# Power.net
KiCad netlist of a schematic drawn in Altium Designer
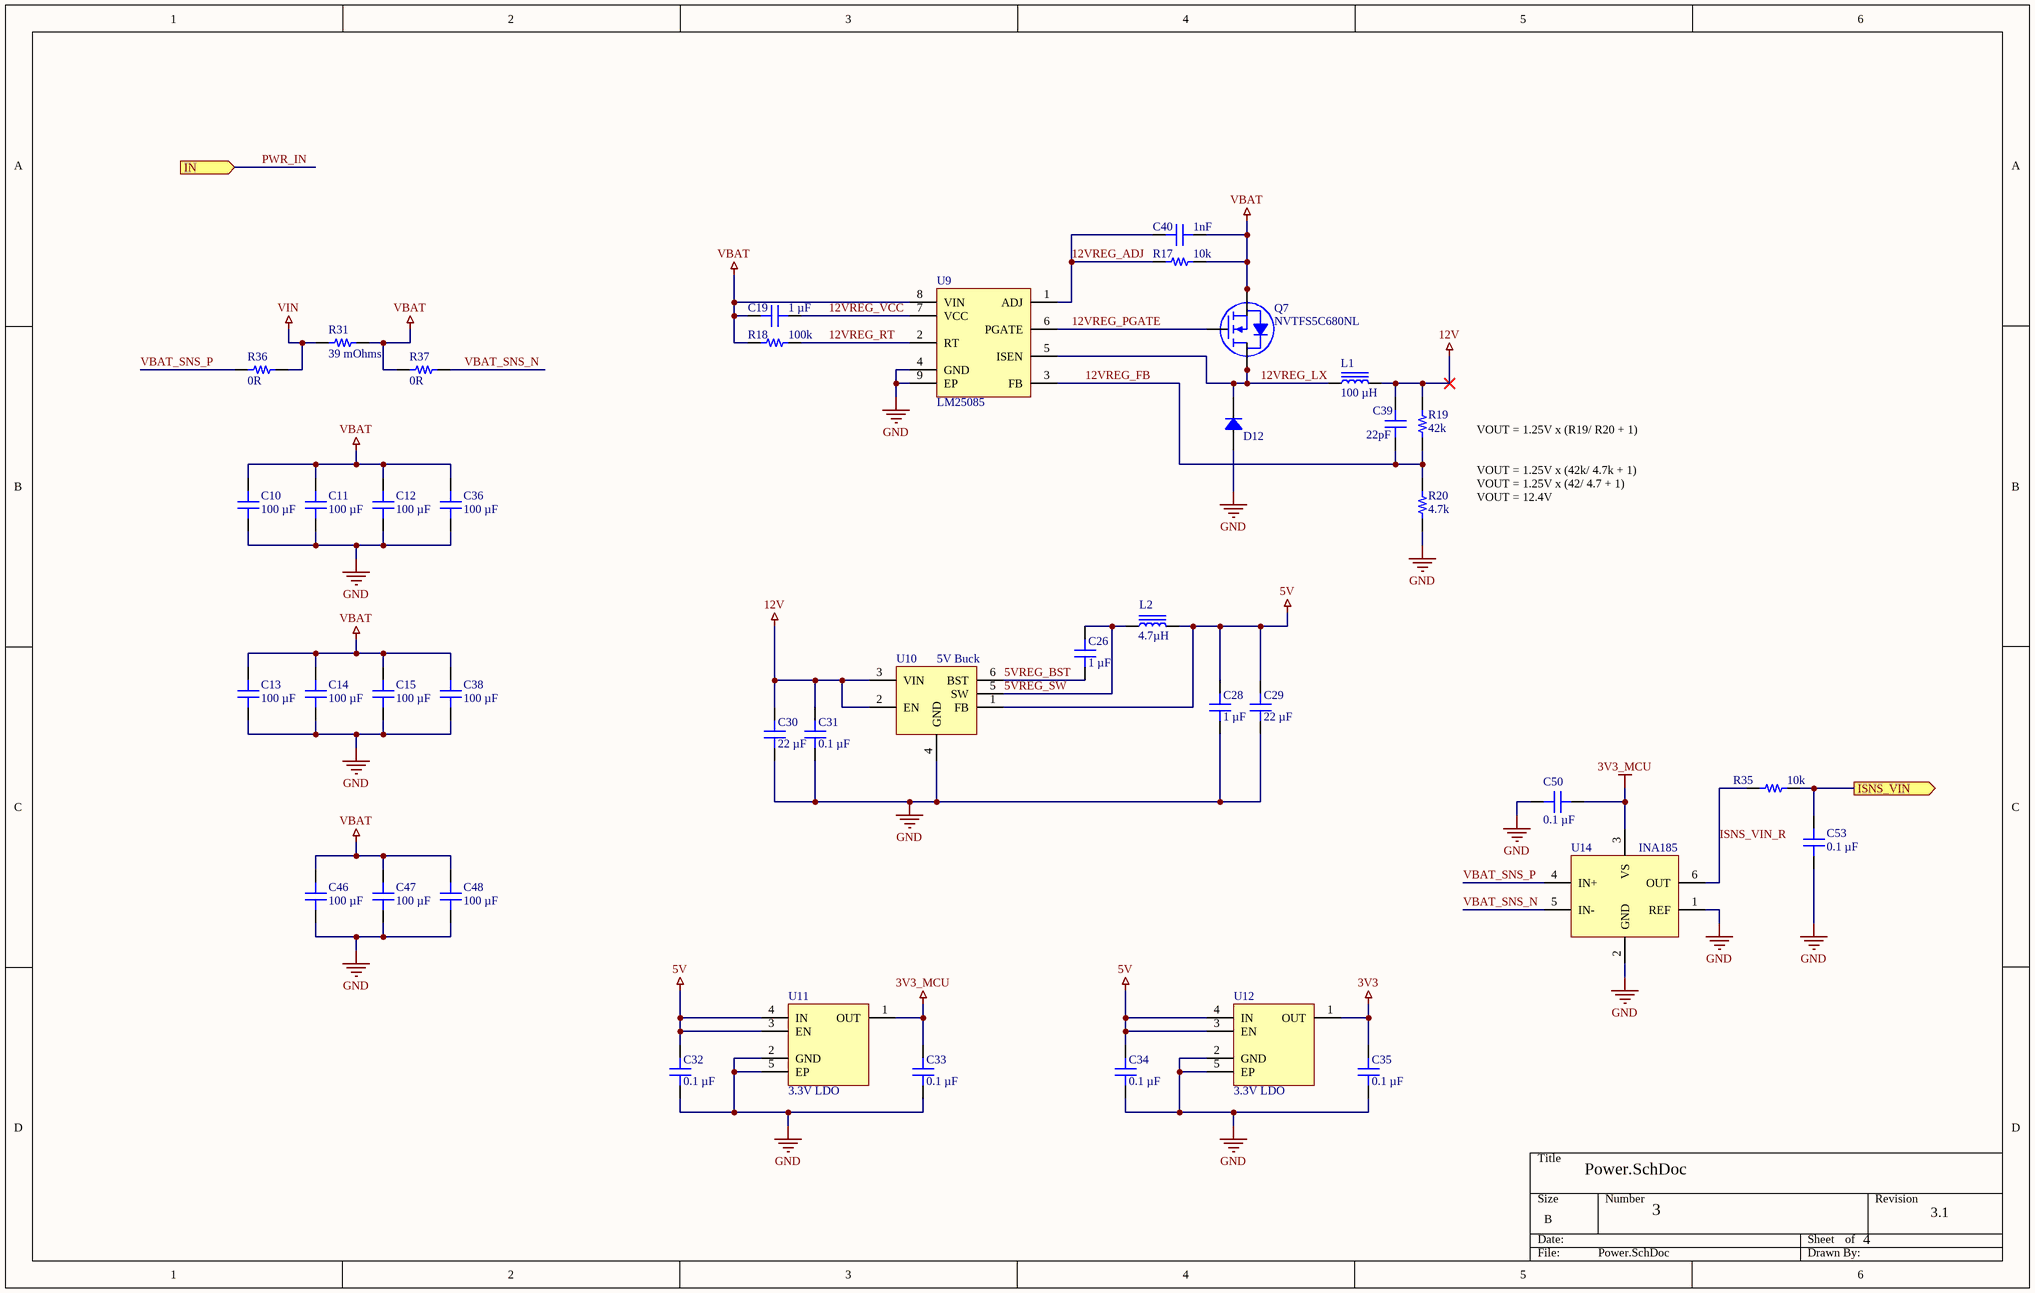
[diagram p0: Power.SchDoc]

(export (version "E")
  (design (tool "Eeschema 10.0.6"))
  (components
    (comp (ref "C10")
      (value "100 µF")
      (footprint "CAP 1210_3225 - 1MM")
      (description "CAP CER 100UF 16V X5R 1210")
      (fields (field (name "PART NUMBER") "MSASE32MAB5107MPNA01") (field (name "MANUFACTURER") "Taiyo Yuden"))
      (libsource (lib "Celestial Altium Library - altium_library") (part "Capacitor"))
    )
    (comp (ref "C11")
      (value "100 µF")
      (footprint "CAP 1210_3225 - 1MM")
      (description "CAP CER 100UF 16V X5R 1210")
      (fields (field (name "PART NUMBER") "MSASE32MAB5107MPNA01") (field (name "MANUFACTURER") "Taiyo Yuden"))
      (libsource (lib "Celestial Altium Library - altium_library") (part "Capacitor"))
    )
    (comp (ref "C12")
      (value "100 µF")
      (footprint "CAP 1210_3225 - 1MM")
      (description "CAP CER 100UF 16V X5R 1210")
      (fields (field (name "PART NUMBER") "MSASE32MAB5107MPNA01") (field (name "MANUFACTURER") "Taiyo Yuden"))
      (libsource (lib "Celestial Altium Library - altium_library") (part "Capacitor"))
    )
    (comp (ref "C13")
      (value "100 µF")
      (footprint "CAP 1210_3225 - 1MM")
      (description "CAP CER 100UF 16V X5R 1210")
      (fields (field (name "PART NUMBER") "MSASE32MAB5107MPNA01") (field (name "MANUFACTURER") "Taiyo Yuden"))
      (libsource (lib "Celestial Altium Library - altium_library") (part "Capacitor"))
    )
    (comp (ref "C14")
      (value "100 µF")
      (footprint "CAP 1210_3225 - 1MM")
      (description "CAP CER 100UF 16V X5R 1210")
      (fields (field (name "PART NUMBER") "MSASE32MAB5107MPNA01") (field (name "MANUFACTURER") "Taiyo Yuden"))
      (libsource (lib "Celestial Altium Library - altium_library") (part "Capacitor"))
    )
    (comp (ref "C15")
      (value "100 µF")
      (footprint "CAP 1210_3225 - 1MM")
      (description "CAP CER 100UF 16V X5R 1210")
      (fields (field (name "PART NUMBER") "MSASE32MAB5107MPNA01") (field (name "MANUFACTURER") "Taiyo Yuden"))
      (libsource (lib "Celestial Altium Library - altium_library") (part "Capacitor"))
    )
    (comp (ref "C19")
      (value "1 µF")
      (footprint "CAP 0402_1005")
      (description "CAP CER 0.1UF 16V X7R 0402")
      (fields (field (name "PART NUMBER") "C0402C104K4RACAUTO") (field (name "MANUFACTURER") "KEMET"))
      (libsource (lib "Celestial Altium Library - altium_library") (part "Capacitor"))
    )
    (comp (ref "C26")
      (value "1 µF")
      (footprint "CAP 0402_1005")
      (description "CAP CER 0.1UF 16V X7R 0402")
      (fields (field (name "PART NUMBER") "C0402C104K4RACAUTO") (field (name "MANUFACTURER") "KEMET"))
      (libsource (lib "Celestial Altium Library - altium_library") (part "Capacitor"))
    )
    (comp (ref "C28")
      (value "1 µF")
      (footprint "CAP 0402_1005")
      (description "CAP CER 0.1UF 16V X7R 0402")
      (fields (field (name "PART NUMBER") "C0402C104K4RACAUTO") (field (name "MANUFACTURER") "KEMET"))
      (libsource (lib "Celestial Altium Library - altium_library") (part "Capacitor"))
    )
    (comp (ref "C29")
      (value "22 µF")
      (footprint "CAP 0402_1005")
      (description "CAP CER 0.1UF 16V X7R 0402")
      (fields (field (name "PART NUMBER") "C0402C104K4RACAUTO") (field (name "MANUFACTURER") "KEMET"))
      (libsource (lib "Celestial Altium Library - altium_library") (part "Capacitor"))
    )
    (comp (ref "C30")
      (value "22 µF")
      (footprint "CAP 0603_1608")
      (description "CAP CER 47UF 6.3V X5R 0603")
      (fields
        (field (name "PART NUMBER") "C0603B476M007T")
        (field (name "MANUFACTURER") "Holy Stone Enterprise Co., Ltd.")
      )
      (libsource (lib "Celestial Altium Library - altium_library") (part "Capacitor"))
    )
    (comp (ref "C31")
      (value "0.1 µF")
      (footprint "CAP 0402_1005")
      (description "CAP CER 0.1UF 16V X7R 0402")
      (fields (field (name "PART NUMBER") "C0402C104K4RACAUTO") (field (name "MANUFACTURER") "KEMET"))
      (libsource (lib "Celestial Altium Library - altium_library") (part "Capacitor"))
    )
    (comp (ref "C32")
      (value "0.1 µF")
      (footprint "CAP 0402_1005")
      (description "CAP CER 0.1UF 16V X7R 0402")
      (fields (field (name "PART NUMBER") "C0402C104K4RACAUTO") (field (name "MANUFACTURER") "KEMET"))
      (libsource (lib "Celestial Altium Library - altium_library") (part "Capacitor"))
    )
    (comp (ref "C33")
      (value "0.1 µF")
      (footprint "CAP 0402_1005")
      (description "CAP CER 0.1UF 16V X7R 0402")
      (fields (field (name "PART NUMBER") "C0402C104K4RACAUTO") (field (name "MANUFACTURER") "KEMET"))
      (libsource (lib "Celestial Altium Library - altium_library") (part "Capacitor"))
    )
    (comp (ref "C34")
      (value "0.1 µF")
      (footprint "CAP 0402_1005")
      (description "CAP CER 0.1UF 16V X7R 0402")
      (fields (field (name "PART NUMBER") "C0402C104K4RACAUTO") (field (name "MANUFACTURER") "KEMET"))
      (libsource (lib "Celestial Altium Library - altium_library") (part "Capacitor"))
    )
    (comp (ref "C35")
      (value "0.1 µF")
      (footprint "CAP 0402_1005")
      (description "CAP CER 0.1UF 16V X7R 0402")
      (fields (field (name "PART NUMBER") "C0402C104K4RACAUTO") (field (name "MANUFACTURER") "KEMET"))
      (libsource (lib "Celestial Altium Library - altium_library") (part "Capacitor"))
    )
    (comp (ref "C36")
      (value "100 µF")
      (footprint "CAP 1210_3225 - 1MM")
      (description "CAP CER 100UF 16V X5R 1210")
      (fields (field (name "PART NUMBER") "MSASE32MAB5107MPNA01") (field (name "MANUFACTURER") "Taiyo Yuden"))
      (libsource (lib "Celestial Altium Library - altium_library") (part "Capacitor"))
    )
    (comp (ref "C38")
      (value "100 µF")
      (footprint "CAP 1210_3225 - 1MM")
      (description "CAP CER 100UF 16V X5R 1210")
      (fields (field (name "PART NUMBER") "MSASE32MAB5107MPNA01") (field (name "MANUFACTURER") "Taiyo Yuden"))
      (libsource (lib "Celestial Altium Library - altium_library") (part "Capacitor"))
    )
    (comp (ref "C39")
      (value "22pF")
      (footprint "CAP 0402_1005")
      (description "CAP CER 0.1UF 16V X7R 0402")
      (fields (field (name "PART NUMBER") "C0402C104K4RACAUTO") (field (name "MANUFACTURER") "KEMET"))
      (libsource (lib "Celestial Altium Library - altium_library") (part "Capacitor"))
    )
    (comp (ref "C40")
      (value "1nF")
      (footprint "CAP 0402_1005")
      (description "CAP CER 0.1UF 16V X7R 0402")
      (fields (field (name "PART NUMBER") "C0402C104K4RACAUTO") (field (name "MANUFACTURER") "KEMET"))
      (libsource (lib "Celestial Altium Library - altium_library") (part "Capacitor"))
    )
    (comp (ref "C46")
      (value "100 µF")
      (footprint "CAP 1210_3225 - 1MM")
      (description "CAP CER 100UF 16V X5R 1210")
      (fields (field (name "PART NUMBER") "MSASE32MAB5107MPNA01") (field (name "MANUFACTURER") "Taiyo Yuden"))
      (libsource (lib "Celestial Altium Library - altium_library") (part "Capacitor"))
    )
    (comp (ref "C47")
      (value "100 µF")
      (footprint "CAP 1210_3225 - 1MM")
      (description "CAP CER 100UF 16V X5R 1210")
      (fields (field (name "PART NUMBER") "MSASE32MAB5107MPNA01") (field (name "MANUFACTURER") "Taiyo Yuden"))
      (libsource (lib "Celestial Altium Library - altium_library") (part "Capacitor"))
    )
    (comp (ref "C48")
      (value "100 µF")
      (footprint "CAP 1210_3225 - 1MM")
      (description "CAP CER 100UF 16V X5R 1210")
      (fields (field (name "PART NUMBER") "MSASE32MAB5107MPNA01") (field (name "MANUFACTURER") "Taiyo Yuden"))
      (libsource (lib "Celestial Altium Library - altium_library") (part "Capacitor"))
    )
    (comp (ref "C50")
      (value "0.1 µF")
      (footprint "CAP 0402_1005")
      (description "CAP CER 0.1UF 16V X7R 0402")
      (fields (field (name "PART NUMBER") "C0402C104K4RACAUTO") (field (name "MANUFACTURER") "KEMET"))
      (libsource (lib "Celestial Altium Library - altium_library") (part "Capacitor"))
    )
    (comp (ref "C53")
      (value "0.1 µF")
      (footprint "CAP 0402_1005")
      (description "CAP CER 0.1UF 16V X7R 0402")
      (fields (field (name "PART NUMBER") "C0402C104K4RACAUTO") (field (name "MANUFACTURER") "KEMET"))
      (libsource (lib "Celestial Altium Library - altium_library") (part "Capacitor"))
    )
    (comp (ref "D12")
      (value "SE10FGHM3/H")
      (footprint "SMF DO-219AB")
      (description "DIODE GEN PURP 400V 1A DO219AB")
      (fields (field (name "MANUFACTURER") "Vishay Semiconductor Diodes Division"))
      (libsource (lib "Celestial Altium Library - altium_library") (part "Diode"))
    )
    (comp (ref "L1")
      (value "100 µH")
      (footprint "TDK VLCF4028-2")
      (description "FIXED IND 100UH 330MA 1 OHM SMD")
      (fields
        (field (name "PART NUMBER") "VLCF4028T-101MR33-2")
        (field (name "MANUFACTURER") "TDK Corporation")
      )
      (libsource (lib "Celestial Altium Library - altium_library") (part "Inductor"))
    )
    (comp (ref "L2")
      (value "4.7µH")
      (footprint "IND 1008_2520")
      (description "FIXED IND 4.7UH 1A 110 MOHM SMD")
      (fields (field (name "PART NUMBER") "MLP2520S4R7ST0S1") (field (name "MANUFACTURER") "TDK Corporation"))
      (libsource (lib "Celestial Altium Library - altium_library") (part "Inductor"))
    )
    (comp (ref "Q7")
      (value "NVTFS5C680NL")
      (footprint "NVTFS015N04CTAG")
      (description "N-FET")
      (libsource (lib "IC") (part "NVTFS5C680NL"))
    )
    (comp (ref "R17")
      (value "10k")
      (footprint "RES 0402_1005")
      (description "RES 14.3K OHM 1% 1/10W 0402")
      (fields
        (field (name "PART NUMBER") "RK73H1ETTP1432F")
        (field (name "MANUFACTURER") "KOA Speer Electronics, Inc.")
      )
      (libsource (lib "Celestial Altium Library - altium_library") (part "Resistor"))
    )
    (comp (ref "R18")
      (value "100k")
      (footprint "RES 0402_1005")
      (description "RES 14.3K OHM 1% 1/10W 0402")
      (fields
        (field (name "PART NUMBER") "RK73H1ETTP1432F")
        (field (name "MANUFACTURER") "KOA Speer Electronics, Inc.")
      )
      (libsource (lib "Celestial Altium Library - altium_library") (part "Resistor"))
    )
    (comp (ref "R19")
      (value "42k")
      (footprint "RES 0402_1005")
      (description "RES 14.3K OHM 1% 1/10W 0402")
      (fields
        (field (name "PART NUMBER") "RK73H1ETTP1432F")
        (field (name "MANUFACTURER") "KOA Speer Electronics, Inc.")
      )
      (libsource (lib "Celestial Altium Library - altium_library") (part "Resistor"))
    )
    (comp (ref "R20")
      (value "4.7k")
      (footprint "RES 0402_1005")
      (description "RES 14.3K OHM 1% 1/10W 0402")
      (fields
        (field (name "PART NUMBER") "RK73H1ETTP1432F")
        (field (name "MANUFACTURER") "KOA Speer Electronics, Inc.")
      )
      (libsource (lib "Celestial Altium Library - altium_library") (part "Resistor"))
    )
    (comp (ref "R31")
      (value "39 mOhms")
      (footprint "RES 1206_3216")
      (description "RES 0.039 OHM 1% 3/4W 1206")
      (fields (field (name "PART NUMBER") "KRL1632E-M-R039-F-T5") (field (name "MANUFACTURER") "Susumu"))
      (libsource (lib "Celestial Altium Library - altium_library") (part "Resistor"))
    )
    (comp (ref "R35")
      (value "10k")
      (footprint "RES 0402_1005")
      (description "RES 14.3K OHM 1% 1/10W 0402")
      (fields
        (field (name "PART NUMBER") "RK73H1ETTP1432F")
        (field (name "MANUFACTURER") "KOA Speer Electronics, Inc.")
      )
      (libsource (lib "Celestial Altium Library - altium_library") (part "Resistor"))
    )
    (comp (ref "R36")
      (value "0R")
      (footprint "RES 0201_0603")
      (description "RES SMD 10 OHM 1% 1/20W 0201")
      (fields
        (field (name "PART NUMBER") "CRG0201F10R")
        (field (name "MANUFACTURER") "TE Connectivity Passive Product")
      )
      (libsource (lib "Celestial Altium Library - altium_library") (part "Resistor"))
    )
    (comp (ref "R37")
      (value "0R")
      (footprint "RES 0201_0603")
      (description "RES SMD 10 OHM 1% 1/20W 0201")
      (fields
        (field (name "PART NUMBER") "CRG0201F10R")
        (field (name "MANUFACTURER") "TE Connectivity Passive Product")
      )
      (libsource (lib "Celestial Altium Library - altium_library") (part "Resistor"))
    )
    (comp (ref "U9")
      (value "LM25085")
      (footprint "8_WSON_3x3_0.5mm")
      (description "PFET Buck Controller")
      (libsource (lib "IC") (part "LM25085"))
    )
    (comp (ref "U10")
      (value "5V Buck")
      (footprint "TSOT-26-6 - 3.2mm")
      (description "5V fixed step down Buck")
      (libsource (lib "IC") (part "AP63205WU-7"))
    )
    (comp (ref "U11") (value "3.3V LDO") (footprint "XDFN-4") (libsource (lib "IC") (part "TLV74033PDQNR")))
    (comp (ref "U12") (value "3.3V LDO") (footprint "XDFN-4") (libsource (lib "IC") (part "TLV74033PDQNR")))
    (comp (ref "U14")
      (value "INA185")
      (footprint "TI SC70-6 DCK")
      (description "INA185A2")
      (libsource (lib "IC") (part "INA185"))
    )
  )
  (nets
    (net (code "1") (name "/5VREG_BST") (class "Default")
      (node (ref "C26") (pin "1") (pinfunction "1_1") (pintype "passive"))
      (node (ref "U10") (pin "6") (pinfunction "BST_6") (pintype "passive"))
    )
    (net (code "2") (name "/5VREG_SW") (class "Default")
      (node (ref "C26") (pin "2") (pinfunction "2_2") (pintype "passive"))
      (node (ref "L2") (pin "1") (pinfunction "1_1") (pintype "passive"))
      (node (ref "U10") (pin "5") (pinfunction "SW_5") (pintype "passive"))
    )
    (net (code "3") (name "/12VREG_ADJ") (class "Default")
      (node (ref "C40") (pin "1") (pinfunction "1_1") (pintype "passive"))
      (node (ref "R17") (pin "1") (pinfunction "1_1") (pintype "passive"))
      (node (ref "U9") (pin "1") (pinfunction "ADJ_1") (pintype "passive"))
    )
    (net (code "4") (name "/12VREG_FB") (class "Default")
      (node (ref "C39") (pin "1") (pinfunction "1_1") (pintype "passive"))
      (node (ref "R19") (pin "1") (pinfunction "1_1") (pintype "passive"))
      (node (ref "R20") (pin "2") (pinfunction "2_2") (pintype "passive"))
      (node (ref "U9") (pin "3") (pinfunction "FB_3") (pintype "passive"))
    )
    (net (code "5") (name "/12VREG_LX") (class "Default")
      (node (ref "D12") (pin "2") (pinfunction "2_2") (pintype "passive"))
      (node (ref "L1") (pin "1") (pinfunction "1_1") (pintype "passive"))
      (node (ref "Q7") (pin "5") (pinfunction "D_5") (pintype "passive"))
      (node (ref "Q7") (pin "6") (pinfunction "D_6") (pintype "passive"))
      (node (ref "Q7") (pin "7") (pinfunction "D_7") (pintype "passive"))
      (node (ref "Q7") (pin "8") (pinfunction "D_8") (pintype "passive"))
      (node (ref "U9") (pin "5") (pinfunction "ISEN_5") (pintype "passive"))
    )
    (net (code "6") (name "/12VREG_PGATE") (class "Default")
      (node (ref "Q7") (pin "4") (pinfunction "G_4") (pintype "passive"))
      (node (ref "U9") (pin "6") (pinfunction "PGATE_6") (pintype "passive"))
    )
    (net (code "7") (name "/12VREG_RT") (class "Default")
      (node (ref "R18") (pin "2") (pinfunction "2_2") (pintype "passive"))
      (node (ref "U9") (pin "2") (pinfunction "RT_2") (pintype "passive"))
    )
    (net (code "8") (name "/12VREG_VCC") (class "Default")
      (node (ref "C19") (pin "2") (pinfunction "2_2") (pintype "passive"))
      (node (ref "U9") (pin "7") (pinfunction "VCC_7") (pintype "passive"))
    )
    (net (code "9") (name "/ISNS_VIN") (class "Default")
      (node (ref "C53") (pin "1") (pinfunction "1_1") (pintype "passive"))
      (node (ref "R35") (pin "2") (pinfunction "2_2") (pintype "passive"))
    )
    (net (code "10") (name "/ISNS_VIN_R") (class "Default")
      (node (ref "R35") (pin "1") (pinfunction "1_1") (pintype "passive"))
      (node (ref "U14") (pin "6") (pinfunction "OUT_6") (pintype "passive"))
    )
    (net (code "12") (name "/VBAT_SNS_N") (class "Default")
      (node (ref "R37") (pin "2") (pinfunction "2_2") (pintype "passive"))
      (node (ref "U14") (pin "5") (pinfunction "IN-_5") (pintype "passive"))
    )
    (net (code "13") (name "/VBAT_SNS_P") (class "Default")
      (node (ref "R36") (pin "1") (pinfunction "1_1") (pintype "passive"))
      (node (ref "U14") (pin "4") (pinfunction "IN+_4") (pintype "passive"))
    )
    (net (code "14") (name "3V3") (class "Default")
      (node (ref "C35") (pin "2") (pinfunction "2_2") (pintype "passive"))
      (node (ref "U12") (pin "1") (pinfunction "OUT_1") (pintype "passive"))
    )
    (net (code "15") (name "3V3_MCU") (class "Default")
      (node (ref "C33") (pin "2") (pinfunction "2_2") (pintype "passive"))
      (node (ref "C50") (pin "1") (pinfunction "1_1") (pintype "passive"))
      (node (ref "U11") (pin "1") (pinfunction "OUT_1") (pintype "passive"))
      (node (ref "U14") (pin "3") (pinfunction "VS_3") (pintype "passive"))
    )
    (net (code "16") (name "5V") (class "Default")
      (node (ref "C28") (pin "2") (pinfunction "2_2") (pintype "passive"))
      (node (ref "C29") (pin "2") (pinfunction "2_2") (pintype "passive"))
      (node (ref "C32") (pin "2") (pinfunction "2_2") (pintype "passive"))
      (node (ref "C34") (pin "2") (pinfunction "2_2") (pintype "passive"))
      (node (ref "L2") (pin "2") (pinfunction "2_2") (pintype "passive"))
      (node (ref "U10") (pin "1") (pinfunction "FB_1") (pintype "passive"))
      (node (ref "U11") (pin "3") (pinfunction "EN_3") (pintype "passive"))
      (node (ref "U11") (pin "4") (pinfunction "IN_4") (pintype "passive"))
      (node (ref "U12") (pin "3") (pinfunction "EN_3") (pintype "passive"))
      (node (ref "U12") (pin "4") (pinfunction "IN_4") (pintype "passive"))
    )
    (net (code "17") (name "12V") (class "Default")
      (node (ref "C30") (pin "2") (pinfunction "2_2") (pintype "passive"))
      (node (ref "C31") (pin "2") (pinfunction "2_2") (pintype "passive"))
      (node (ref "C39") (pin "2") (pinfunction "2_2") (pintype "passive"))
      (node (ref "L1") (pin "2") (pinfunction "2_2") (pintype "passive"))
      (node (ref "R19") (pin "2") (pinfunction "2_2") (pintype "passive"))
      (node (ref "U10") (pin "2") (pinfunction "EN_2") (pintype "passive"))
      (node (ref "U10") (pin "3") (pinfunction "VIN_3") (pintype "passive"))
    )
    (net (code "18") (name "GND") (class "Default")
      (node (ref "C10") (pin "1") (pinfunction "1_1") (pintype "passive"))
      (node (ref "C11") (pin "1") (pinfunction "1_1") (pintype "passive"))
      (node (ref "C12") (pin "1") (pinfunction "1_1") (pintype "passive"))
      (node (ref "C13") (pin "1") (pinfunction "1_1") (pintype "passive"))
      (node (ref "C14") (pin "1") (pinfunction "1_1") (pintype "passive"))
      (node (ref "C15") (pin "1") (pinfunction "1_1") (pintype "passive"))
      (node (ref "C28") (pin "1") (pinfunction "1_1") (pintype "passive"))
      (node (ref "C29") (pin "1") (pinfunction "1_1") (pintype "passive"))
      (node (ref "C30") (pin "1") (pinfunction "1_1") (pintype "passive"))
      (node (ref "C31") (pin "1") (pinfunction "1_1") (pintype "passive"))
      (node (ref "C32") (pin "1") (pinfunction "1_1") (pintype "passive"))
      (node (ref "C33") (pin "1") (pinfunction "1_1") (pintype "passive"))
      (node (ref "C34") (pin "1") (pinfunction "1_1") (pintype "passive"))
      (node (ref "C35") (pin "1") (pinfunction "1_1") (pintype "passive"))
      (node (ref "C36") (pin "1") (pinfunction "1_1") (pintype "passive"))
      (node (ref "C38") (pin "1") (pinfunction "1_1") (pintype "passive"))
      (node (ref "C46") (pin "1") (pinfunction "1_1") (pintype "passive"))
      (node (ref "C47") (pin "1") (pinfunction "1_1") (pintype "passive"))
      (node (ref "C48") (pin "1") (pinfunction "1_1") (pintype "passive"))
      (node (ref "C50") (pin "2") (pinfunction "2_2") (pintype "passive"))
      (node (ref "C53") (pin "2") (pinfunction "2_2") (pintype "passive"))
      (node (ref "D12") (pin "1") (pinfunction "1_1") (pintype "passive"))
      (node (ref "R20") (pin "1") (pinfunction "1_1") (pintype "passive"))
      (node (ref "U10") (pin "4") (pinfunction "GND_4") (pintype "passive"))
      (node (ref "U11") (pin "2") (pinfunction "GND_2") (pintype "passive"))
      (node (ref "U11") (pin "5") (pinfunction "EP_5") (pintype "passive"))
      (node (ref "U12") (pin "2") (pinfunction "GND_2") (pintype "passive"))
      (node (ref "U12") (pin "5") (pinfunction "EP_5") (pintype "passive"))
      (node (ref "U14") (pin "1") (pinfunction "REF_1") (pintype "passive"))
      (node (ref "U14") (pin "2") (pinfunction "GND_2") (pintype "passive"))
      (node (ref "U9") (pin "4") (pinfunction "GND_4") (pintype "passive"))
      (node (ref "U9") (pin "9") (pinfunction "EP_9") (pintype "passive"))
    )
    (net (code "19") (name "VBAT") (class "Default")
      (node (ref "C10") (pin "2") (pinfunction "2_2") (pintype "passive"))
      (node (ref "C11") (pin "2") (pinfunction "2_2") (pintype "passive"))
      (node (ref "C12") (pin "2") (pinfunction "2_2") (pintype "passive"))
      (node (ref "C13") (pin "2") (pinfunction "2_2") (pintype "passive"))
      (node (ref "C14") (pin "2") (pinfunction "2_2") (pintype "passive"))
      (node (ref "C15") (pin "2") (pinfunction "2_2") (pintype "passive"))
      (node (ref "C19") (pin "1") (pinfunction "1_1") (pintype "passive"))
      (node (ref "C36") (pin "2") (pinfunction "2_2") (pintype "passive"))
      (node (ref "C38") (pin "2") (pinfunction "2_2") (pintype "passive"))
      (node (ref "C40") (pin "2") (pinfunction "2_2") (pintype "passive"))
      (node (ref "C46") (pin "2") (pinfunction "2_2") (pintype "passive"))
      (node (ref "C47") (pin "2") (pinfunction "2_2") (pintype "passive"))
      (node (ref "C48") (pin "2") (pinfunction "2_2") (pintype "passive"))
      (node (ref "Q7") (pin "1") (pinfunction "S_1") (pintype "passive"))
      (node (ref "Q7") (pin "2") (pinfunction "S_2") (pintype "passive"))
      (node (ref "Q7") (pin "3") (pinfunction "S_3") (pintype "passive"))
      (node (ref "R17") (pin "2") (pinfunction "2_2") (pintype "passive"))
      (node (ref "R18") (pin "1") (pinfunction "1_1") (pintype "passive"))
      (node (ref "R31") (pin "2") (pinfunction "2_2") (pintype "passive"))
      (node (ref "R37") (pin "1") (pinfunction "1_1") (pintype "passive"))
      (node (ref "U9") (pin "8") (pinfunction "VIN_8") (pintype "passive"))
    )
    (net (code "20") (name "VIN") (class "Default")
      (node (ref "R31") (pin "1") (pinfunction "1_1") (pintype "passive"))
      (node (ref "R36") (pin "2") (pinfunction "2_2") (pintype "passive"))
    )
  )
)
